# rpi2_relay2.net
KiCad netlist of a schematic drawn in EAGLE
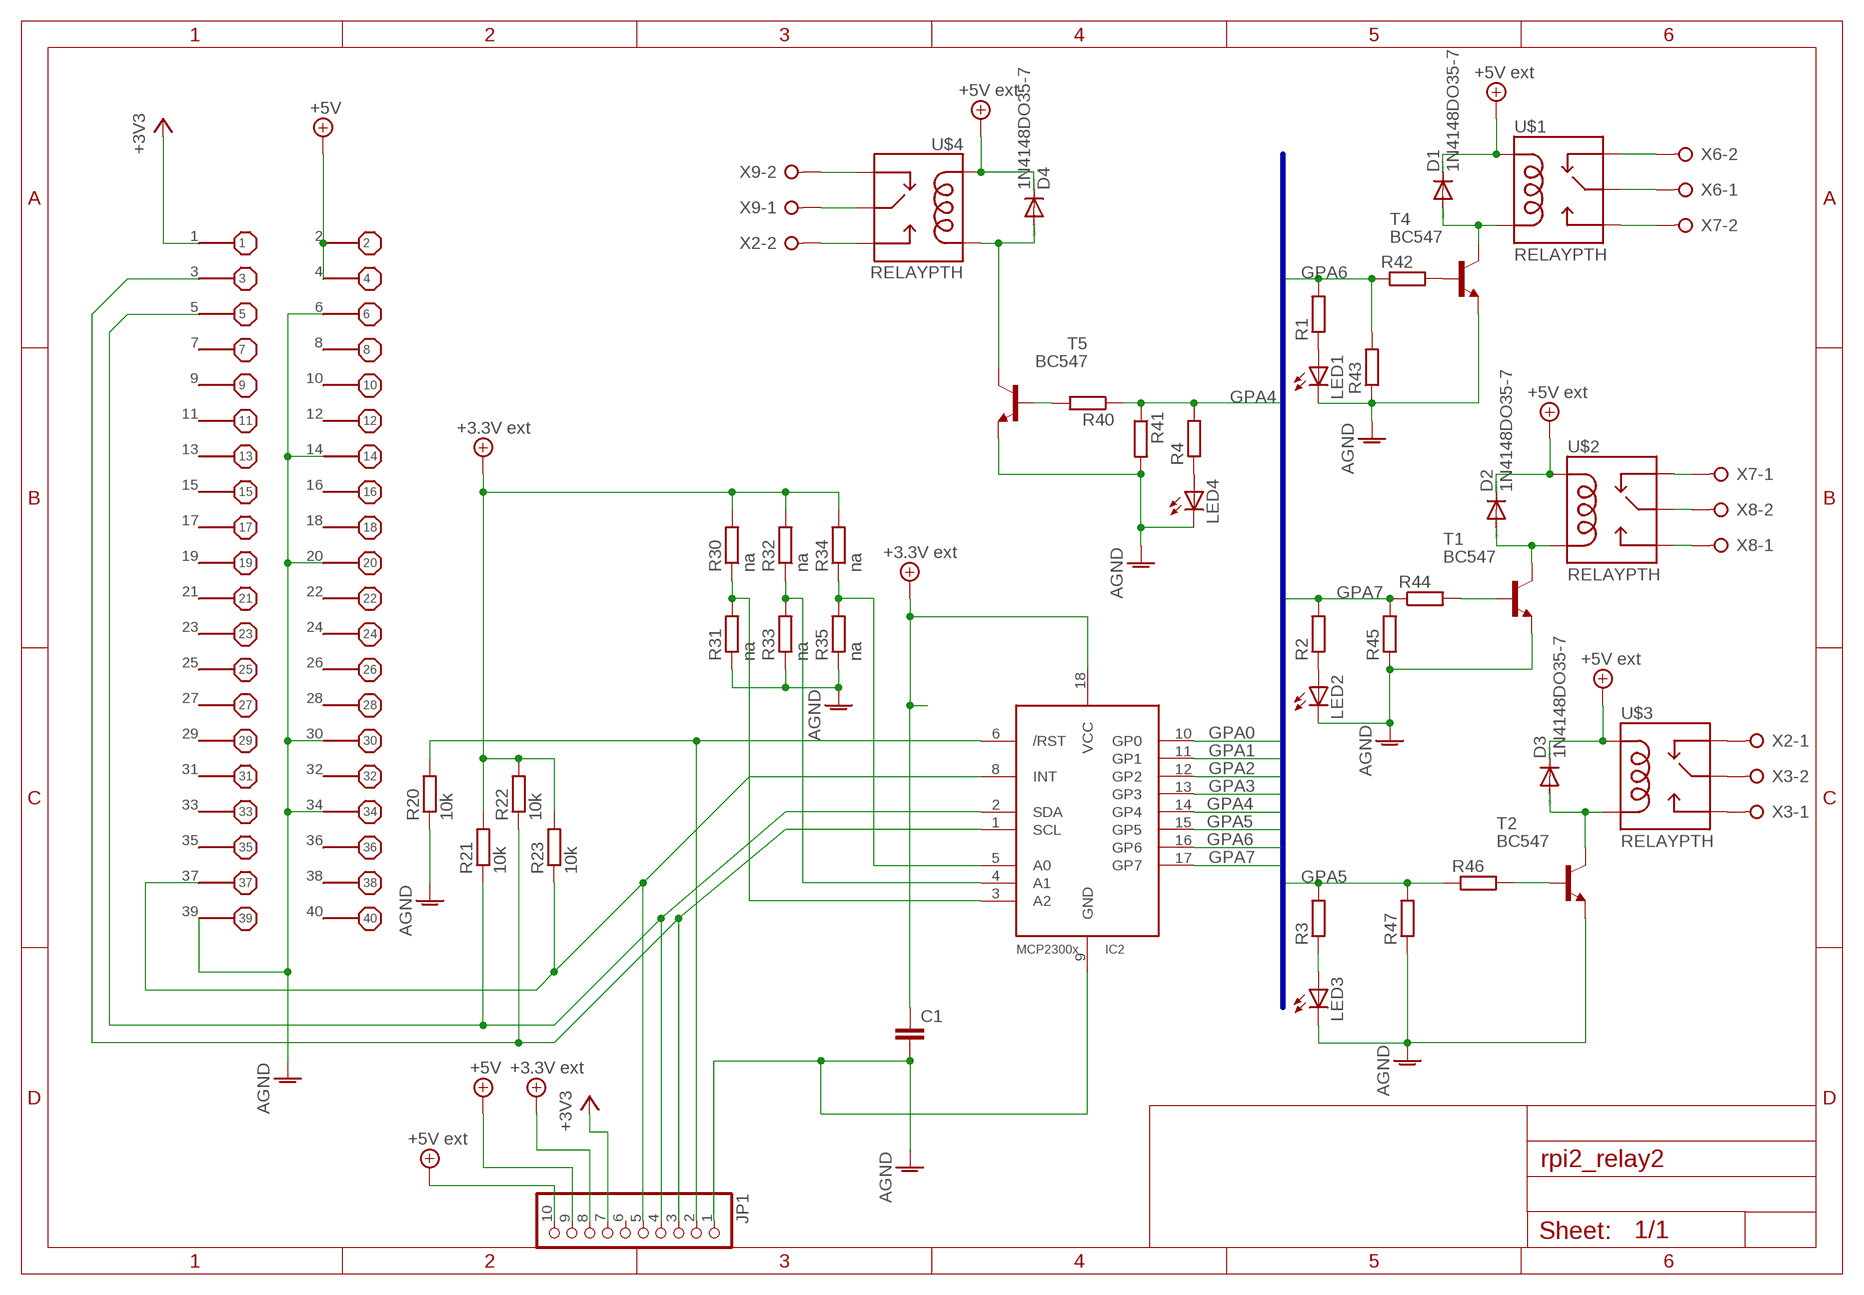
[diagram p0: schematic, sheet 1]

(export (version "E")
  (design (tool "Eeschema 10.0.6"))
  (components
    (comp (ref "C1")
      (value "C-EUC1210")
      (footprint "eagle-import:C1210")
      (libsource (lib "eagle-import") (part "C-EUC1210"))
    )
    (comp (ref "D1")
      (value "1N4148DO35-7")
      (footprint "eagle-import:DO35-7")
      (libsource (lib "eagle-import") (part "1N4148DO35-7"))
    )
    (comp (ref "D2")
      (value "1N4148DO35-7")
      (footprint "eagle-import:DO35-7")
      (libsource (lib "eagle-import") (part "1N4148DO35-7"))
    )
    (comp (ref "D3")
      (value "1N4148DO35-7")
      (footprint "eagle-import:DO35-7")
      (libsource (lib "eagle-import") (part "1N4148DO35-7"))
    )
    (comp (ref "D4")
      (value "1N4148DO35-7")
      (footprint "eagle-import:DO35-7")
      (libsource (lib "eagle-import") (part "1N4148DO35-7"))
    )
    (comp (ref "IC2")
      (value "MCP23008/P")
      (footprint "eagle-import:DIL18")
      (libsource (lib "eagle-import") (part "MCP23008/P"))
    )
    (comp (ref "JP1")
      (value "PINHD-1X10")
      (footprint "eagle-import:1X10")
      (libsource (lib "eagle-import") (part "PINHD-1X10"))
    )
    (comp (ref "LED1")
      (value "LEDCHIP-LED0805")
      (footprint "eagle-import:CHIP-LED0805")
      (libsource (lib "eagle-import") (part "LEDCHIP-LED0805"))
    )
    (comp (ref "LED2")
      (value "LEDCHIP-LED0805")
      (footprint "eagle-import:CHIP-LED0805")
      (libsource (lib "eagle-import") (part "LEDCHIP-LED0805"))
    )
    (comp (ref "LED3")
      (value "LEDCHIP-LED0805")
      (footprint "eagle-import:CHIP-LED0805")
      (libsource (lib "eagle-import") (part "LEDCHIP-LED0805"))
    )
    (comp (ref "LED4")
      (value "LEDCHIP-LED0805")
      (footprint "eagle-import:CHIP-LED0805")
      (libsource (lib "eagle-import") (part "LEDCHIP-LED0805"))
    )
    (comp (ref "R1")
      (value "R-EU_R0805")
      (footprint "eagle-import:R0805")
      (libsource (lib "eagle-import") (part "R-EU_R0805"))
    )
    (comp (ref "R2")
      (value "R-EU_R0805")
      (footprint "eagle-import:R0805")
      (libsource (lib "eagle-import") (part "R-EU_R0805"))
    )
    (comp (ref "R3")
      (value "R-EU_R0805")
      (footprint "eagle-import:R0805")
      (libsource (lib "eagle-import") (part "R-EU_R0805"))
    )
    (comp (ref "R4")
      (value "R-EU_R0805")
      (footprint "eagle-import:R0805")
      (libsource (lib "eagle-import") (part "R-EU_R0805"))
    )
    (comp (ref "R20")
      (value "10k")
      (footprint "eagle-import:R0805")
      (libsource (lib "eagle-import") (part "R-EU_R0805"))
    )
    (comp (ref "R21")
      (value "10k")
      (footprint "eagle-import:R0805")
      (libsource (lib "eagle-import") (part "R-EU_R0805"))
    )
    (comp (ref "R22")
      (value "10k")
      (footprint "eagle-import:R0805")
      (libsource (lib "eagle-import") (part "R-EU_R0805"))
    )
    (comp (ref "R23")
      (value "10k")
      (footprint "eagle-import:R0805")
      (libsource (lib "eagle-import") (part "R-EU_R0805"))
    )
    (comp (ref "R30")
      (value "na")
      (footprint "eagle-import:R0805")
      (libsource (lib "eagle-import") (part "R-EU_R0805"))
    )
    (comp (ref "R31")
      (value "na")
      (footprint "eagle-import:R0805")
      (libsource (lib "eagle-import") (part "R-EU_R0805"))
    )
    (comp (ref "R32")
      (value "na")
      (footprint "eagle-import:R0805")
      (libsource (lib "eagle-import") (part "R-EU_R0805"))
    )
    (comp (ref "R33")
      (value "na")
      (footprint "eagle-import:R0805")
      (libsource (lib "eagle-import") (part "R-EU_R0805"))
    )
    (comp (ref "R34")
      (value "na")
      (footprint "eagle-import:R0805")
      (libsource (lib "eagle-import") (part "R-EU_R0805"))
    )
    (comp (ref "R35")
      (value "na")
      (footprint "eagle-import:R0805")
      (libsource (lib "eagle-import") (part "R-EU_R0805"))
    )
    (comp (ref "R40")
      (value "R-EU_R0805")
      (footprint "eagle-import:R0805")
      (libsource (lib "eagle-import") (part "R-EU_R0805"))
    )
    (comp (ref "R41")
      (value "R-EU_R0805")
      (footprint "eagle-import:R0805")
      (libsource (lib "eagle-import") (part "R-EU_R0805"))
    )
    (comp (ref "R42")
      (value "R-EU_R0805")
      (footprint "eagle-import:R0805")
      (libsource (lib "eagle-import") (part "R-EU_R0805"))
    )
    (comp (ref "R43")
      (value "R-EU_R0805")
      (footprint "eagle-import:R0805")
      (libsource (lib "eagle-import") (part "R-EU_R0805"))
    )
    (comp (ref "R44")
      (value "R-EU_R0805")
      (footprint "eagle-import:R0805")
      (libsource (lib "eagle-import") (part "R-EU_R0805"))
    )
    (comp (ref "R45")
      (value "R-EU_R0805")
      (footprint "eagle-import:R0805")
      (libsource (lib "eagle-import") (part "R-EU_R0805"))
    )
    (comp (ref "R46")
      (value "R-EU_R0805")
      (footprint "eagle-import:R0805")
      (libsource (lib "eagle-import") (part "R-EU_R0805"))
    )
    (comp (ref "R47")
      (value "R-EU_R0805")
      (footprint "eagle-import:R0805")
      (libsource (lib "eagle-import") (part "R-EU_R0805"))
    )
    (comp (ref "T1")
      (value "BC547")
      (footprint "eagle-import:TO92")
      (libsource (lib "eagle-import") (part "BC547"))
    )
    (comp (ref "T2")
      (value "BC547")
      (footprint "eagle-import:TO92")
      (libsource (lib "eagle-import") (part "BC547"))
    )
    (comp (ref "T4")
      (value "BC547")
      (footprint "eagle-import:TO92")
      (libsource (lib "eagle-import") (part "BC547"))
    )
    (comp (ref "T5")
      (value "BC547")
      (footprint "eagle-import:TO92")
      (libsource (lib "eagle-import") (part "BC547"))
    )
    (comp (ref "U$1")
      (value "RELAYPTH")
      (footprint "eagle-import:SRD-05VDC-SL-C")
      (libsource (lib "eagle-import") (part "RELAYPTH"))
    )
    (comp (ref "U$2")
      (value "RELAYPTH")
      (footprint "eagle-import:SRD-05VDC-SL-C")
      (libsource (lib "eagle-import") (part "RELAYPTH"))
    )
    (comp (ref "U$3")
      (value "RELAYPTH")
      (footprint "eagle-import:SRD-05VDC-SL-C")
      (libsource (lib "eagle-import") (part "RELAYPTH"))
    )
    (comp (ref "U$4")
      (value "RELAYPTH")
      (footprint "eagle-import:SRD-05VDC-SL-C")
      (libsource (lib "eagle-import") (part "RELAYPTH"))
    )
    (comp (ref "X1")
      (value "B+_GPIO")
      (footprint "eagle-import:B+_GPIO")
      (libsource (lib "eagle-import") (part "B+_GPIO"))
    )
    (comp (ref "X2")
      (value "W237-02P")
      (footprint "eagle-import:W237-132")
      (libsource (lib "eagle-import") (part "W237-02P"))
    )
    (comp (ref "X3")
      (value "W237-02P")
      (footprint "eagle-import:W237-132")
      (libsource (lib "eagle-import") (part "W237-02P"))
    )
    (comp (ref "X6")
      (value "W237-02P")
      (footprint "eagle-import:W237-132")
      (libsource (lib "eagle-import") (part "W237-02P"))
    )
    (comp (ref "X7")
      (value "W237-02P")
      (footprint "eagle-import:W237-132")
      (libsource (lib "eagle-import") (part "W237-02P"))
    )
    (comp (ref "X8")
      (value "W237-02P")
      (footprint "eagle-import:W237-132")
      (libsource (lib "eagle-import") (part "W237-02P"))
    )
    (comp (ref "X9")
      (value "W237-02P")
      (footprint "eagle-import:W237-132")
      (libsource (lib "eagle-import") (part "W237-02P"))
    )
  )
  (nets
    (net (code "1") (name "+3.3V ext") (class "Default")
      (node (ref "C1") (pin "1") (pinfunction "1_1") (pintype "passive"))
      (node (ref "IC2") (pin "18") (pinfunction "VCC_18") (pintype "power_in"))
      (node (ref "JP1") (pin "8") (pinfunction "8_8") (pintype "passive"))
      (node (ref "R21") (pin "2") (pinfunction "2_2") (pintype "passive"))
      (node (ref "R22") (pin "2") (pinfunction "2_2") (pintype "passive"))
      (node (ref "R23") (pin "2") (pinfunction "2_2") (pintype "passive"))
      (node (ref "R30") (pin "2") (pinfunction "2_2") (pintype "passive"))
      (node (ref "R32") (pin "2") (pinfunction "2_2") (pintype "passive"))
      (node (ref "R34") (pin "2") (pinfunction "2_2") (pintype "passive"))
    )
    (net (code "2") (name "+3V3") (class "Default")
      (node (ref "JP1") (pin "7") (pinfunction "7_7") (pintype "passive"))
      (node (ref "X1") (pin "1") (pinfunction "P$1_1") (pintype "bidirectional"))
    )
    (net (code "3") (name "+5V") (class "Default")
      (node (ref "JP1") (pin "9") (pinfunction "9_9") (pintype "passive"))
      (node (ref "X1") (pin "2") (pinfunction "P$1_2") (pintype "bidirectional"))
      (node (ref "X1") (pin "4") (pinfunction "P$1_4") (pintype "bidirectional"))
    )
    (net (code "4") (name "+5V ext") (class "Default")
      (node (ref "D1") (pin "C") (pinfunction "C_C") (pintype "passive"))
      (node (ref "D2") (pin "C") (pinfunction "C_C") (pintype "passive"))
      (node (ref "D3") (pin "C") (pinfunction "C_C") (pintype "passive"))
      (node (ref "D4") (pin "C") (pinfunction "C_C") (pintype "passive"))
      (node (ref "JP1") (pin "10") (pinfunction "10_10") (pintype "passive"))
      (node (ref "U$1") (pin "COIL1") (pinfunction "COIL1_COIL1") (pintype "bidirectional"))
      (node (ref "U$2") (pin "COIL1") (pinfunction "COIL1_COIL1") (pintype "bidirectional"))
      (node (ref "U$3") (pin "COIL1") (pinfunction "COIL1_COIL1") (pintype "bidirectional"))
      (node (ref "U$4") (pin "COIL1") (pinfunction "COIL1_COIL1") (pintype "bidirectional"))
    )
    (net (code "5") (name "/GPA0") (class "Default")
      (node (ref "IC2") (pin "10") (pinfunction "GP0_10") (pintype "bidirectional"))
    )
    (net (code "6") (name "/GPA1") (class "Default")
      (node (ref "IC2") (pin "11") (pinfunction "GP1_11") (pintype "bidirectional"))
    )
    (net (code "7") (name "/GPA2") (class "Default")
      (node (ref "IC2") (pin "12") (pinfunction "GP2_12") (pintype "bidirectional"))
    )
    (net (code "8") (name "/GPA3") (class "Default")
      (node (ref "IC2") (pin "13") (pinfunction "GP3_13") (pintype "bidirectional"))
    )
    (net (code "9") (name "/GPA4") (class "Default")
      (node (ref "IC2") (pin "14") (pinfunction "GP4_14") (pintype "bidirectional"))
      (node (ref "R4") (pin "2") (pinfunction "2_2") (pintype "passive"))
      (node (ref "R40") (pin "1") (pinfunction "1_1") (pintype "passive"))
      (node (ref "R41") (pin "1") (pinfunction "1_1") (pintype "passive"))
    )
    (net (code "10") (name "/GPA5") (class "Default")
      (node (ref "IC2") (pin "15") (pinfunction "GP5_15") (pintype "bidirectional"))
      (node (ref "R3") (pin "2") (pinfunction "2_2") (pintype "passive"))
      (node (ref "R46") (pin "1") (pinfunction "1_1") (pintype "passive"))
      (node (ref "R47") (pin "2") (pinfunction "2_2") (pintype "passive"))
    )
    (net (code "11") (name "/GPA6") (class "Default")
      (node (ref "IC2") (pin "16") (pinfunction "GP6_16") (pintype "bidirectional"))
      (node (ref "R1") (pin "2") (pinfunction "2_2") (pintype "passive"))
      (node (ref "R42") (pin "1") (pinfunction "1_1") (pintype "passive"))
      (node (ref "R43") (pin "2") (pinfunction "2_2") (pintype "passive"))
    )
    (net (code "12") (name "/GPA7") (class "Default")
      (node (ref "IC2") (pin "17") (pinfunction "GP7_17") (pintype "bidirectional"))
      (node (ref "R2") (pin "2") (pinfunction "2_2") (pintype "passive"))
      (node (ref "R44") (pin "1") (pinfunction "1_1") (pintype "passive"))
      (node (ref "R45") (pin "2") (pinfunction "2_2") (pintype "passive"))
    )
    (net (code "13") (name "AGND") (class "Default")
      (node (ref "C1") (pin "2") (pinfunction "2_2") (pintype "passive"))
      (node (ref "IC2") (pin "9") (pinfunction "GND_9") (pintype "power_in"))
      (node (ref "JP1") (pin "1") (pinfunction "1_1") (pintype "passive"))
      (node (ref "LED1") (pin "C") (pinfunction "C_C") (pintype "passive"))
      (node (ref "LED2") (pin "C") (pinfunction "C_C") (pintype "passive"))
      (node (ref "LED3") (pin "C") (pinfunction "C_C") (pintype "passive"))
      (node (ref "LED4") (pin "C") (pinfunction "C_C") (pintype "passive"))
      (node (ref "R20") (pin "1") (pinfunction "1_1") (pintype "passive"))
      (node (ref "R31") (pin "1") (pinfunction "1_1") (pintype "passive"))
      (node (ref "R33") (pin "1") (pinfunction "1_1") (pintype "passive"))
      (node (ref "R35") (pin "1") (pinfunction "1_1") (pintype "passive"))
      (node (ref "R41") (pin "2") (pinfunction "2_2") (pintype "passive"))
      (node (ref "R43") (pin "1") (pinfunction "1_1") (pintype "passive"))
      (node (ref "R45") (pin "1") (pinfunction "1_1") (pintype "passive"))
      (node (ref "R47") (pin "1") (pinfunction "1_1") (pintype "passive"))
      (node (ref "T1") (pin "1") (pinfunction "E_1") (pintype "passive"))
      (node (ref "T2") (pin "1") (pinfunction "E_1") (pintype "passive"))
      (node (ref "T4") (pin "1") (pinfunction "E_1") (pintype "passive"))
      (node (ref "T5") (pin "1") (pinfunction "E_1") (pintype "passive"))
      (node (ref "X1") (pin "14") (pinfunction "P$1_14") (pintype "bidirectional"))
      (node (ref "X1") (pin "20") (pinfunction "P$1_20") (pintype "bidirectional"))
      (node (ref "X1") (pin "30") (pinfunction "P$1_30") (pintype "bidirectional"))
      (node (ref "X1") (pin "34") (pinfunction "P$1_34") (pintype "bidirectional"))
      (node (ref "X1") (pin "39") (pinfunction "P$1_39") (pintype "bidirectional"))
      (node (ref "X1") (pin "6") (pinfunction "P$1_6") (pintype "bidirectional"))
    )
    (net (code "14") (name "Net-(IC2-A0)") (class "Default")
      (node (ref "IC2") (pin "5") (pinfunction "A0_5") (pintype "input"))
      (node (ref "R34") (pin "1") (pinfunction "1_1") (pintype "passive"))
      (node (ref "R35") (pin "2") (pinfunction "2_2") (pintype "passive"))
    )
    (net (code "15") (name "Net-(IC2-A1)") (class "Default")
      (node (ref "IC2") (pin "4") (pinfunction "A1_4") (pintype "input"))
      (node (ref "R32") (pin "1") (pinfunction "1_1") (pintype "passive"))
      (node (ref "R33") (pin "2") (pinfunction "2_2") (pintype "passive"))
    )
    (net (code "16") (name "Net-(IC2-A2)") (class "Default")
      (node (ref "IC2") (pin "3") (pinfunction "A2_3") (pintype "input"))
      (node (ref "R30") (pin "1") (pinfunction "1_1") (pintype "passive"))
      (node (ref "R31") (pin "2") (pinfunction "2_2") (pintype "passive"))
    )
    (net (code "17") (name "Net-(IC2-INT)") (class "Default")
      (node (ref "IC2") (pin "8") (pinfunction "INT_8") (pintype "output"))
      (node (ref "JP1") (pin "5") (pinfunction "5_5") (pintype "passive"))
      (node (ref "R23") (pin "1") (pinfunction "1_1") (pintype "passive"))
      (node (ref "X1") (pin "37") (pinfunction "P$1_37") (pintype "bidirectional"))
    )
    (net (code "18") (name "Net-(IC2-SCL)") (class "Default")
      (node (ref "IC2") (pin "1") (pinfunction "SCL_1") (pintype "bidirectional"))
      (node (ref "JP1") (pin "3") (pinfunction "3_3") (pintype "passive"))
      (node (ref "R22") (pin "1") (pinfunction "1_1") (pintype "passive"))
      (node (ref "X1") (pin "3") (pinfunction "P$1_3") (pintype "bidirectional"))
    )
    (net (code "19") (name "Net-(IC2-SDA)") (class "Default")
      (node (ref "IC2") (pin "2") (pinfunction "SDA_2") (pintype "bidirectional"))
      (node (ref "JP1") (pin "4") (pinfunction "4_4") (pintype "passive"))
      (node (ref "R21") (pin "1") (pinfunction "1_1") (pintype "passive"))
      (node (ref "X1") (pin "5") (pinfunction "P$1_5") (pintype "bidirectional"))
    )
    (net (code "20") (name "Net-(IC2-{slash}RST)") (class "Default")
      (node (ref "IC2") (pin "6") (pinfunction "/RST_6") (pintype "input"))
      (node (ref "JP1") (pin "2") (pinfunction "2_2") (pintype "passive"))
      (node (ref "R20") (pin "2") (pinfunction "2_2") (pintype "passive"))
    )
    (net (code "21") (name "Net-(LED1-PadA)") (class "Default")
      (node (ref "LED1") (pin "A") (pinfunction "A_A") (pintype "passive"))
      (node (ref "R1") (pin "1") (pinfunction "1_1") (pintype "passive"))
    )
    (net (code "22") (name "Net-(LED2-PadA)") (class "Default")
      (node (ref "LED2") (pin "A") (pinfunction "A_A") (pintype "passive"))
      (node (ref "R2") (pin "1") (pinfunction "1_1") (pintype "passive"))
    )
    (net (code "23") (name "Net-(LED3-PadA)") (class "Default")
      (node (ref "LED3") (pin "A") (pinfunction "A_A") (pintype "passive"))
      (node (ref "R3") (pin "1") (pinfunction "1_1") (pintype "passive"))
    )
    (net (code "24") (name "Net-(LED4-PadA)") (class "Default")
      (node (ref "LED4") (pin "A") (pinfunction "A_A") (pintype "passive"))
      (node (ref "R4") (pin "1") (pinfunction "1_1") (pintype "passive"))
    )
    (net (code "25") (name "Net-(T1-B)") (class "Default")
      (node (ref "R44") (pin "2") (pinfunction "2_2") (pintype "passive"))
      (node (ref "T1") (pin "2") (pinfunction "B_2") (pintype "passive"))
    )
    (net (code "26") (name "Net-(T1-C)") (class "Default")
      (node (ref "D2") (pin "A") (pinfunction "A_A") (pintype "passive"))
      (node (ref "T1") (pin "3") (pinfunction "C_3") (pintype "passive"))
      (node (ref "U$2") (pin "COIL0") (pinfunction "COIL0_COIL0") (pintype "bidirectional"))
    )
    (net (code "27") (name "Net-(T2-B)") (class "Default")
      (node (ref "R46") (pin "2") (pinfunction "2_2") (pintype "passive"))
      (node (ref "T2") (pin "2") (pinfunction "B_2") (pintype "passive"))
    )
    (net (code "28") (name "Net-(T2-C)") (class "Default")
      (node (ref "D3") (pin "A") (pinfunction "A_A") (pintype "passive"))
      (node (ref "T2") (pin "3") (pinfunction "C_3") (pintype "passive"))
      (node (ref "U$3") (pin "COIL0") (pinfunction "COIL0_COIL0") (pintype "bidirectional"))
    )
    (net (code "29") (name "Net-(T4-B)") (class "Default")
      (node (ref "R42") (pin "2") (pinfunction "2_2") (pintype "passive"))
      (node (ref "T4") (pin "2") (pinfunction "B_2") (pintype "passive"))
    )
    (net (code "30") (name "Net-(T4-C)") (class "Default")
      (node (ref "D1") (pin "A") (pinfunction "A_A") (pintype "passive"))
      (node (ref "T4") (pin "3") (pinfunction "C_3") (pintype "passive"))
      (node (ref "U$1") (pin "COIL0") (pinfunction "COIL0_COIL0") (pintype "bidirectional"))
    )
    (net (code "31") (name "Net-(T5-B)") (class "Default")
      (node (ref "R40") (pin "2") (pinfunction "2_2") (pintype "passive"))
      (node (ref "T5") (pin "2") (pinfunction "B_2") (pintype "passive"))
    )
    (net (code "32") (name "Net-(T5-C)") (class "Default")
      (node (ref "D4") (pin "A") (pinfunction "A_A") (pintype "passive"))
      (node (ref "T5") (pin "3") (pinfunction "C_3") (pintype "passive"))
      (node (ref "U$4") (pin "COIL0") (pinfunction "COIL0_COIL0") (pintype "bidirectional"))
    )
    (net (code "33") (name "Net-(U$1-SWCLOSE)") (class "Default")
      (node (ref "U$1") (pin "SWCLOSED") (pinfunction "SWCLOSE_SWCLOSED") (pintype "bidirectional"))
      (node (ref "X6") (pin "2") (pinfunction "KL_2") (pintype "passive"))
    )
    (net (code "34") (name "Net-(U$2-SWCLOSE)") (class "Default")
      (node (ref "U$2") (pin "SWCLOSED") (pinfunction "SWCLOSE_SWCLOSED") (pintype "bidirectional"))
      (node (ref "X7") (pin "1") (pinfunction "KL_1") (pintype "passive"))
    )
    (net (code "35") (name "Net-(U$3-SWCLOSE)") (class "Default")
      (node (ref "U$3") (pin "SWCLOSED") (pinfunction "SWCLOSE_SWCLOSED") (pintype "bidirectional"))
      (node (ref "X2") (pin "1") (pinfunction "KL_1") (pintype "passive"))
    )
    (net (code "36") (name "Net-(U$4-SWCLOSE)") (class "Default")
      (node (ref "U$4") (pin "SWCLOSED") (pinfunction "SWCLOSE_SWCLOSED") (pintype "bidirectional"))
      (node (ref "X9") (pin "2") (pinfunction "KL_2") (pintype "passive"))
    )
    (net (code "37") (name "Net-(X2B-KL)") (class "Default")
      (node (ref "U$4") (pin "SWOPEN") (pinfunction "SWOPEN_SWOPEN") (pintype "bidirectional"))
      (node (ref "X2") (pin "2") (pinfunction "KL_2") (pintype "passive"))
    )
    (net (code "38") (name "Net-(X3A-KL)") (class "Default")
      (node (ref "U$3") (pin "SWOPEN") (pinfunction "SWOPEN_SWOPEN") (pintype "bidirectional"))
      (node (ref "X3") (pin "1") (pinfunction "KL_1") (pintype "passive"))
    )
    (net (code "39") (name "Net-(X3B-KL)") (class "Default")
      (node (ref "U$3") (pin "SWCOMMON") (pinfunction "SWCOMMON_SWCOMMON") (pintype "bidirectional"))
      (node (ref "X3") (pin "2") (pinfunction "KL_2") (pintype "passive"))
    )
    (net (code "40") (name "Net-(X6A-KL)") (class "Default")
      (node (ref "U$1") (pin "SWCOMMON") (pinfunction "SWCOMMON_SWCOMMON") (pintype "bidirectional"))
      (node (ref "X6") (pin "1") (pinfunction "KL_1") (pintype "passive"))
    )
    (net (code "41") (name "Net-(X7B-KL)") (class "Default")
      (node (ref "U$1") (pin "SWOPEN") (pinfunction "SWOPEN_SWOPEN") (pintype "bidirectional"))
      (node (ref "X7") (pin "2") (pinfunction "KL_2") (pintype "passive"))
    )
    (net (code "42") (name "Net-(X8A-KL)") (class "Default")
      (node (ref "U$2") (pin "SWOPEN") (pinfunction "SWOPEN_SWOPEN") (pintype "bidirectional"))
      (node (ref "X8") (pin "1") (pinfunction "KL_1") (pintype "passive"))
    )
    (net (code "43") (name "Net-(X8B-KL)") (class "Default")
      (node (ref "U$2") (pin "SWCOMMON") (pinfunction "SWCOMMON_SWCOMMON") (pintype "bidirectional"))
      (node (ref "X8") (pin "2") (pinfunction "KL_2") (pintype "passive"))
    )
    (net (code "44") (name "Net-(X9A-KL)") (class "Default")
      (node (ref "U$4") (pin "SWCOMMON") (pinfunction "SWCOMMON_SWCOMMON") (pintype "bidirectional"))
      (node (ref "X9") (pin "1") (pinfunction "KL_1") (pintype "passive"))
    )
    (net (code "45") (name "unconnected-(JP1-Pad6)") (class "Default")
      (node (ref "JP1") (pin "6") (pinfunction "6_6") (pintype "passive"))
    )
    (net (code "46") (name "unconnected-(X1AA-P$1-Pad33)") (class "Default")
      (node (ref "X1") (pin "33") (pinfunction "P$1_33") (pintype "bidirectional"))
    )
    (net (code "47") (name "unconnected-(X1AC-P$1-Pad35)") (class "Default")
      (node (ref "X1") (pin "35") (pinfunction "P$1_35") (pintype "bidirectional"))
    )
    (net (code "48") (name "unconnected-(X1AD-P$1-Pad36)") (class "Default")
      (node (ref "X1") (pin "36") (pinfunction "P$1_36") (pintype "bidirectional"))
    )
    (net (code "49") (name "unconnected-(X1AF-P$1-Pad38)") (class "Default")
      (node (ref "X1") (pin "38") (pinfunction "P$1_38") (pintype "bidirectional"))
    )
    (net (code "50") (name "unconnected-(X1AI-P$1-Pad40)") (class "Default")
      (node (ref "X1") (pin "40") (pinfunction "P$1_40") (pintype "bidirectional"))
    )
    (net (code "51") (name "unconnected-(X1AL-P$1-Pad7)") (class "Default")
      (node (ref "X1") (pin "7") (pinfunction "P$1_7") (pintype "bidirectional"))
    )
    (net (code "52") (name "unconnected-(X1AM-P$1-Pad8)") (class "Default")
      (node (ref "X1") (pin "8") (pinfunction "P$1_8") (pintype "bidirectional"))
    )
    (net (code "53") (name "unconnected-(X1AN-P$1-Pad9)") (class "Default")
      (node (ref "X1") (pin "9") (pinfunction "P$1_9") (pintype "bidirectional"))
    )
    (net (code "54") (name "unconnected-(X1B-P$1-Pad10)") (class "Default")
      (node (ref "X1") (pin "10") (pinfunction "P$1_10") (pintype "bidirectional"))
    )
    (net (code "55") (name "unconnected-(X1C-P$1-Pad11)") (class "Default")
      (node (ref "X1") (pin "11") (pinfunction "P$1_11") (pintype "bidirectional"))
    )
    (net (code "56") (name "unconnected-(X1D-P$1-Pad12)") (class "Default")
      (node (ref "X1") (pin "12") (pinfunction "P$1_12") (pintype "bidirectional"))
    )
    (net (code "57") (name "unconnected-(X1E-P$1-Pad13)") (class "Default")
      (node (ref "X1") (pin "13") (pinfunction "P$1_13") (pintype "bidirectional"))
    )
    (net (code "58") (name "unconnected-(X1G-P$1-Pad15)") (class "Default")
      (node (ref "X1") (pin "15") (pinfunction "P$1_15") (pintype "bidirectional"))
    )
    (net (code "59") (name "unconnected-(X1H-P$1-Pad16)") (class "Default")
      (node (ref "X1") (pin "16") (pinfunction "P$1_16") (pintype "bidirectional"))
    )
    (net (code "60") (name "unconnected-(X1I-P$1-Pad17)") (class "Default")
      (node (ref "X1") (pin "17") (pinfunction "P$1_17") (pintype "bidirectional"))
    )
    (net (code "61") (name "unconnected-(X1J-P$1-Pad18)") (class "Default")
      (node (ref "X1") (pin "18") (pinfunction "P$1_18") (pintype "bidirectional"))
    )
    (net (code "62") (name "unconnected-(X1K-P$1-Pad19)") (class "Default")
      (node (ref "X1") (pin "19") (pinfunction "P$1_19") (pintype "bidirectional"))
    )
    (net (code "63") (name "unconnected-(X1N-P$1-Pad21)") (class "Default")
      (node (ref "X1") (pin "21") (pinfunction "P$1_21") (pintype "bidirectional"))
    )
    (net (code "64") (name "unconnected-(X1O-P$1-Pad22)") (class "Default")
      (node (ref "X1") (pin "22") (pinfunction "P$1_22") (pintype "bidirectional"))
    )
    (net (code "65") (name "unconnected-(X1P-P$1-Pad23)") (class "Default")
      (node (ref "X1") (pin "23") (pinfunction "P$1_23") (pintype "bidirectional"))
    )
    (net (code "66") (name "unconnected-(X1Q-P$1-Pad24)") (class "Default")
      (node (ref "X1") (pin "24") (pinfunction "P$1_24") (pintype "bidirectional"))
    )
    (net (code "67") (name "unconnected-(X1R-P$1-Pad25)") (class "Default")
      (node (ref "X1") (pin "25") (pinfunction "P$1_25") (pintype "bidirectional"))
    )
    (net (code "68") (name "unconnected-(X1S-P$1-Pad26)") (class "Default")
      (node (ref "X1") (pin "26") (pinfunction "P$1_26") (pintype "bidirectional"))
    )
    (net (code "69") (name "unconnected-(X1T-P$1-Pad27)") (class "Default")
      (node (ref "X1") (pin "27") (pinfunction "P$1_27") (pintype "bidirectional"))
    )
    (net (code "70") (name "unconnected-(X1U-P$1-Pad28)") (class "Default")
      (node (ref "X1") (pin "28") (pinfunction "P$1_28") (pintype "bidirectional"))
    )
    (net (code "71") (name "unconnected-(X1V-P$1-Pad29)") (class "Default")
      (node (ref "X1") (pin "29") (pinfunction "P$1_29") (pintype "bidirectional"))
    )
    (net (code "72") (name "unconnected-(X1Y-P$1-Pad31)") (class "Default")
      (node (ref "X1") (pin "31") (pinfunction "P$1_31") (pintype "bidirectional"))
    )
    (net (code "73") (name "unconnected-(X1Z-P$1-Pad32)") (class "Default")
      (node (ref "X1") (pin "32") (pinfunction "P$1_32") (pintype "bidirectional"))
    )
  )
)
